# Sheet1.net
KiCad netlist of a schematic drawn in Altium Designer
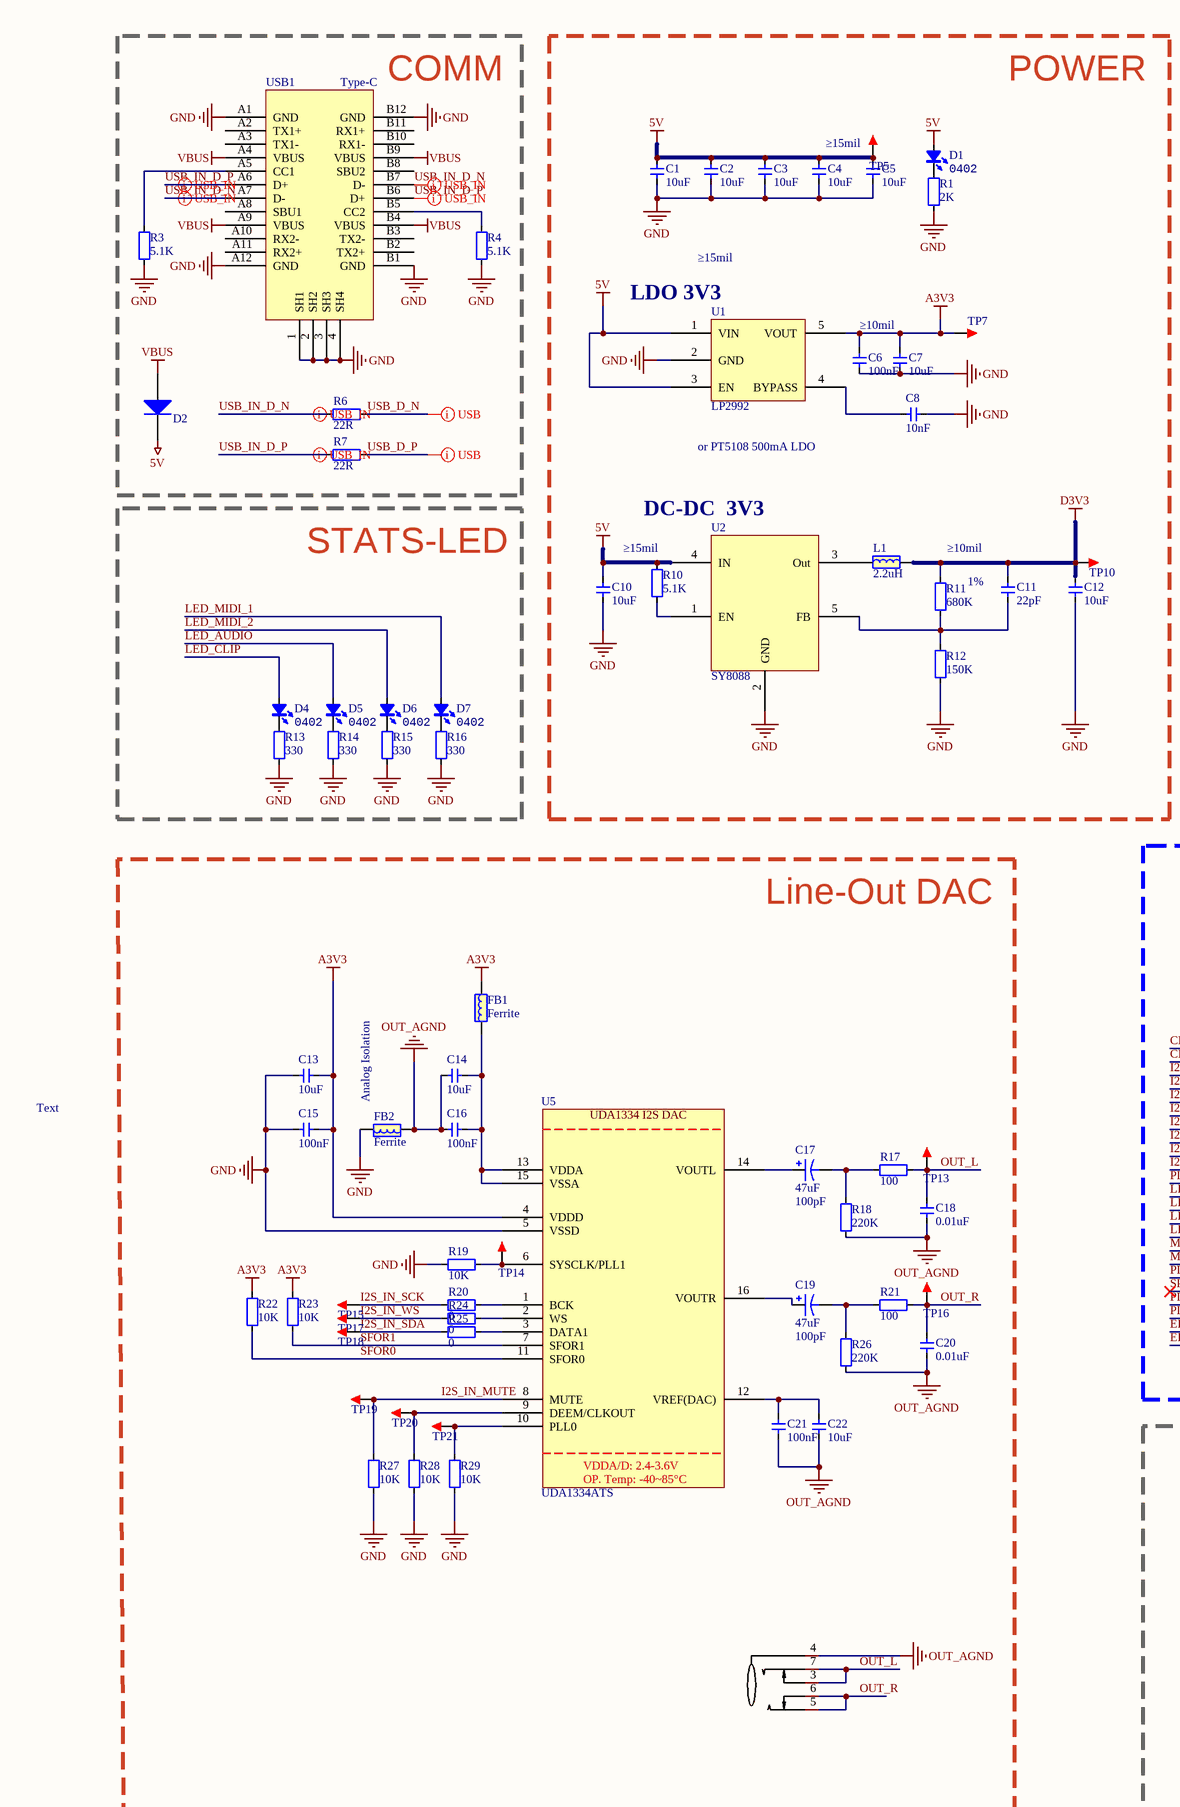
[diagram p0: Sheet1.SchDoc, left]
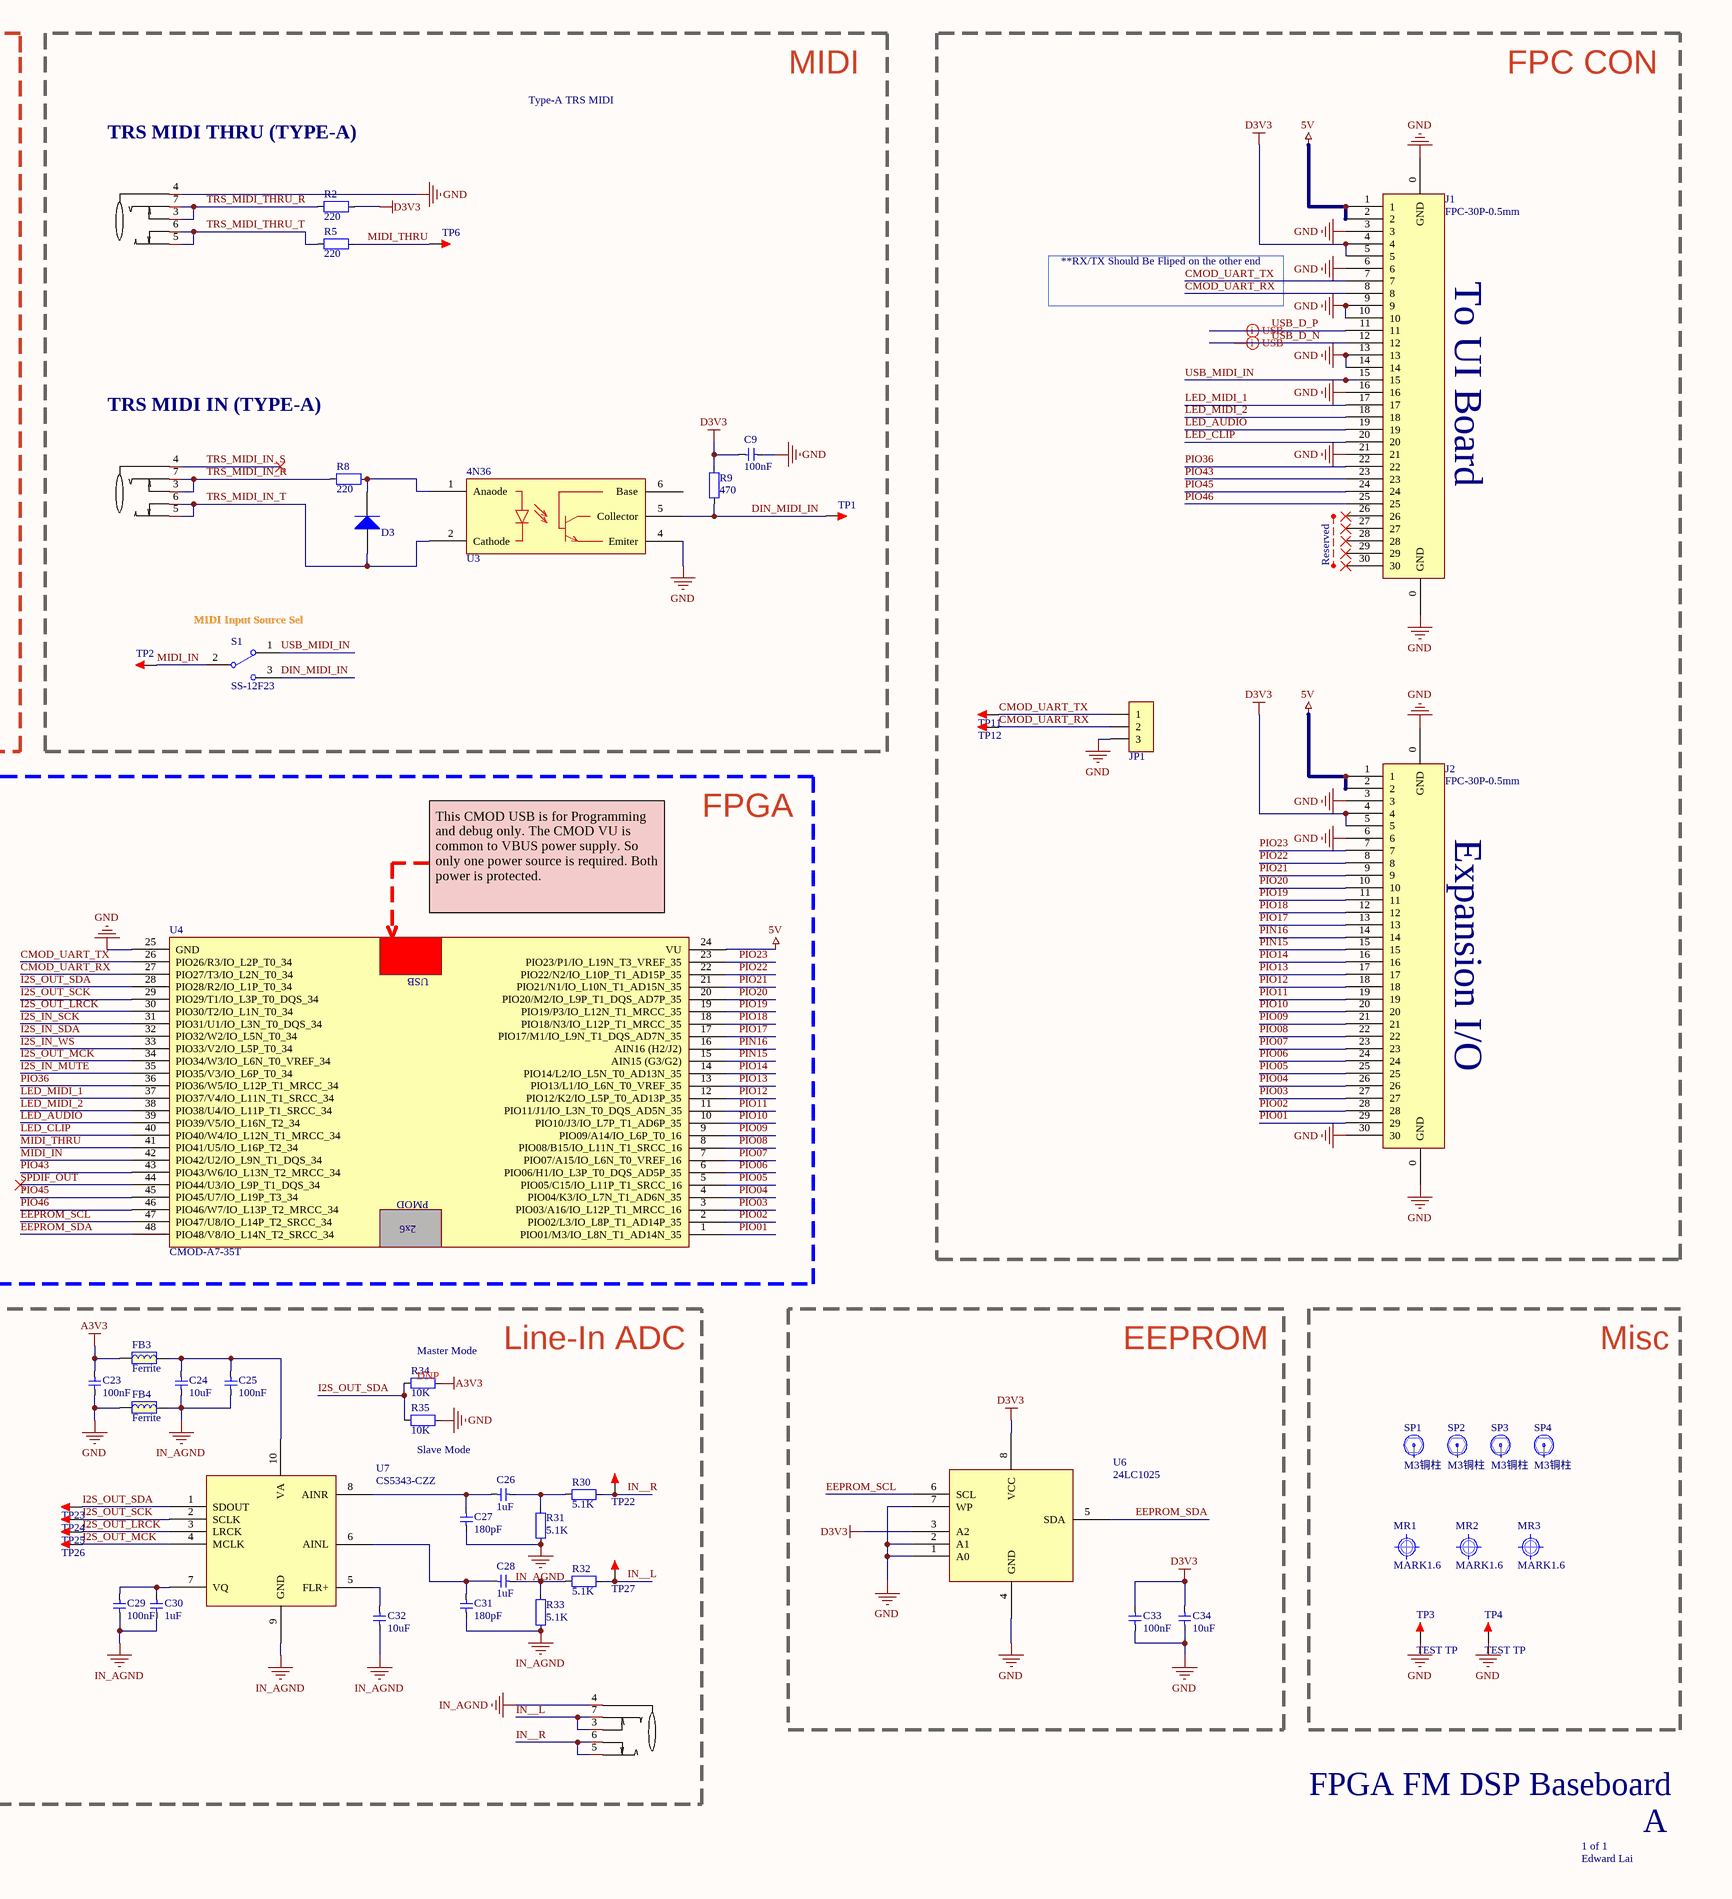
[diagram p1: Sheet1.SchDoc, right]

(export (version "E")
  (design (tool "Eeschema 10.0.6"))
  (components
    (comp (ref "C1")
      (value "10uF")
      (footprint "C0402_L")
      (description "Capacitor")
      (libsource (lib "MyPcbLib") (part "电容-1206"))
    )
    (comp (ref "C2")
      (value "10uF")
      (footprint "C0402_L")
      (description "Capacitor")
      (libsource (lib "MyPcbLib") (part "电容-1206"))
    )
    (comp (ref "C3")
      (value "10uF")
      (footprint "C0402_L")
      (description "Capacitor")
      (libsource (lib "MyPcbLib") (part "电容-1206"))
    )
    (comp (ref "C4")
      (value "10uF")
      (footprint "C0402_L")
      (description "Capacitor")
      (libsource (lib "MyPcbLib") (part "电容-1206"))
    )
    (comp (ref "C5")
      (value "10uF")
      (footprint "C0402_L")
      (description "Capacitor")
      (libsource (lib "MyPcbLib") (part "电容-1206"))
    )
    (comp (ref "C6")
      (value "100nF")
      (footprint "C0402_L")
      (description "Capacitor")
      (libsource (lib "MyPcbLib") (part "电容-0402"))
    )
    (comp (ref "C7")
      (value "10uF")
      (footprint "C0402_L")
      (description "Capacitor")
      (libsource (lib "MyPcbLib") (part "电容-0402"))
    )
    (comp (ref "C8")
      (value "10nF")
      (footprint "C0402_L")
      (description "Capacitor")
      (libsource (lib "MyPcbLib") (part "电容-0402"))
    )
    (comp (ref "C9")
      (value "100nF")
      (footprint "C0402_L")
      (description "Capacitor")
      (libsource (lib "MyPcbLib") (part "电容-0402"))
    )
    (comp (ref "C10")
      (value "10uF")
      (footprint "C0402_L")
      (description "Capacitor")
      (libsource (lib "MyPcbLib") (part "电容-0402"))
    )
    (comp (ref "C11")
      (value "22pF")
      (footprint "C0402_L")
      (description "Capacitor")
      (libsource (lib "MyPcbLib") (part "电容-0402"))
    )
    (comp (ref "C12")
      (value "10uF")
      (footprint "C0402_L")
      (description "Capacitor")
      (libsource (lib "MyPcbLib") (part "电容-0402"))
    )
    (comp (ref "C13")
      (value "10uF")
      (footprint "C0402_L")
      (description "Capacitor")
      (libsource (lib "MyPcbLib") (part "电容-0402"))
    )
    (comp (ref "C14")
      (value "10uF")
      (footprint "C0402_L")
      (description "Capacitor")
      (libsource (lib "MyPcbLib") (part "电容-0402"))
    )
    (comp (ref "C15")
      (value "100nF")
      (footprint "C0402_L")
      (description "Capacitor")
      (libsource (lib "MyPcbLib") (part "电容-0402"))
    )
    (comp (ref "C16")
      (value "100nF")
      (footprint "C0402_L")
      (description "Capacitor")
      (libsource (lib "MyPcbLib") (part "电容-0402"))
    )
    (comp (ref "C17")
      (value "47uF")
      (footprint "CT 5*6 - B")
      (description "Polarized Capacitor SMT")
      (fields (field (name "ALTIUM_VALUE") "100pF") (field (name "PUBLISHER") "Altium Limited"))
      (libsource (lib "Miscellaneous Devices") (part "Cap Pol1"))
    )
    (comp (ref "C18")
      (value "0.01uF")
      (footprint "C0603_L")
      (description "Capacitor")
      (libsource (lib "MyPcbLib") (part "电容-0402"))
    )
    (comp (ref "C19")
      (value "47uF")
      (footprint "CT 5*6 - B")
      (description "Polarized Capacitor SMT")
      (fields (field (name "ALTIUM_VALUE") "100pF") (field (name "PUBLISHER") "Altium Limited"))
      (libsource (lib "Miscellaneous Devices") (part "Cap Pol1"))
    )
    (comp (ref "C20")
      (value "0.01uF")
      (footprint "C0603_L")
      (description "Capacitor")
      (libsource (lib "MyPcbLib") (part "电容-0402"))
    )
    (comp (ref "C21")
      (value "100nF")
      (footprint "C0402_L")
      (description "Capacitor")
      (libsource (lib "MyPcbLib") (part "电容-0402"))
    )
    (comp (ref "C22")
      (value "10uF")
      (footprint "C0402_L")
      (description "Capacitor")
      (libsource (lib "MyPcbLib") (part "电容-0402"))
    )
    (comp (ref "C23")
      (value "100nF")
      (footprint "C0402_L")
      (description "Capacitor")
      (libsource (lib "MyPcbLib") (part "电容-0402"))
    )
    (comp (ref "C24")
      (value "10uF")
      (footprint "C0402_L")
      (description "Capacitor")
      (libsource (lib "MyPcbLib") (part "电容-0402"))
    )
    (comp (ref "C25")
      (value "100nF")
      (footprint "C0402_L")
      (description "Capacitor")
      (libsource (lib "MyPcbLib") (part "电容-0402"))
    )
    (comp (ref "C26")
      (value "1uF")
      (footprint "C0402_L")
      (description "Capacitor")
      (libsource (lib "MyPcbLib") (part "电容-0402"))
    )
    (comp (ref "C27")
      (value "180pF")
      (footprint "C0402_L")
      (description "Capacitor")
      (libsource (lib "MyPcbLib") (part "电容-0402"))
    )
    (comp (ref "C28")
      (value "1uF")
      (footprint "C0402_L")
      (description "Capacitor")
      (libsource (lib "MyPcbLib") (part "电容-0402"))
    )
    (comp (ref "C29")
      (value "100nF")
      (footprint "C0402_L")
      (description "Capacitor")
      (libsource (lib "MyPcbLib") (part "电容-0402"))
    )
    (comp (ref "C30")
      (value "1uF")
      (footprint "C0402_L")
      (description "Capacitor")
      (libsource (lib "MyPcbLib") (part "电容-0402"))
    )
    (comp (ref "C31")
      (value "180pF")
      (footprint "C0402_L")
      (description "Capacitor")
      (libsource (lib "MyPcbLib") (part "电容-0402"))
    )
    (comp (ref "C32")
      (value "10uF")
      (footprint "C0402_L")
      (description "Capacitor")
      (libsource (lib "MyPcbLib") (part "电容-0402"))
    )
    (comp (ref "C33")
      (value "100nF")
      (footprint "C0402_L")
      (description "Capacitor")
      (libsource (lib "MyPcbLib") (part "电容-0402"))
    )
    (comp (ref "C34")
      (value "10uF")
      (footprint "C0402_L")
      (description "Capacitor")
      (libsource (lib "MyPcbLib") (part "电容-0402"))
    )
    (comp (ref "CN1")
      (value "PJ-328-5A")
      (footprint "AUDIO-SMD_PJ-328-5A")
      (fields (field (name "MANUFACTURER") "韩国韩荣"))
      (libsource (lib "altium-import") (part "root_0_PJ-328-5A_"))
    )
    (comp (ref "CN2")
      (value "PJ-328-5A")
      (footprint "AUDIO-SMD_PJ-328-5A")
      (fields (field (name "MANUFACTURER") "韩国韩荣"))
      (libsource (lib "altium-import") (part "root_0_PJ-328-5A_"))
    )
    (comp (ref "CN3")
      (value "PJ-328-5A")
      (footprint "AUDIO-SMD_PJ-328-5A")
      (fields (field (name "MANUFACTURER") "韩国韩荣"))
      (libsource (lib "altium-import") (part "root_0_PJ-328-5A_"))
    )
    (comp (ref "CN4")
      (value "PJ-328-5A")
      (footprint "AUDIO-SMD_PJ-328-5A")
      (fields (field (name "MANUFACTURER") "韩国韩荣"))
      (libsource (lib "altium-import") (part "root_0_mirrored_PJ-328-5A_"))
    )
    (comp (ref "D1")
      (value "color?")
      (footprint "LED0603_R")
      (description "LED")
      (fields (field (name "TYPE") "0402"))
      (libsource (lib "KitSprout") (part "LED_0402"))
    )
    (comp (ref "D2")
      (value "二极管-5B5819WS")
      (footprint "SOD-323")
      (description "40V")
      (libsource (lib "MyPcbLib") (part "二极管-5B5817WS"))
    )
    (comp (ref "D3")
      (value "Diode")
      (footprint "SOD-523")
      (description "1N1418")
      (libsource (lib "0.2 - 二极管-TVS-ESD-整流桥") (part "Diode"))
    )
    (comp (ref "D4")
      (value "color?")
      (footprint "LED0603_R")
      (description "LED")
      (fields (field (name "TYPE") "0402"))
      (libsource (lib "KitSprout") (part "LED_0402"))
    )
    (comp (ref "D5")
      (value "color?")
      (footprint "LED0603_G")
      (description "LED")
      (fields (field (name "TYPE") "0402"))
      (libsource (lib "KitSprout") (part "LED_0402"))
    )
    (comp (ref "D6")
      (value "color?")
      (footprint "LED0603_W")
      (description "LED")
      (fields (field (name "TYPE") "0402"))
      (libsource (lib "KitSprout") (part "LED_0402"))
    )
    (comp (ref "D7")
      (value "color?")
      (footprint "LED0603_W")
      (description "LED")
      (fields (field (name "TYPE") "0402"))
      (libsource (lib "KitSprout") (part "LED_0402"))
    )
    (comp (ref "FB1") (value "Ferrite") (footprint "L0402") (libsource (lib "") (part "电感-201612_2")))
    (comp (ref "FB2") (value "Ferrite") (footprint "L0402") (libsource (lib "MyPcbLib") (part "电感-201612")))
    (comp (ref "FB3") (value "Ferrite") (footprint "L0402") (libsource (lib "") (part "电感-201612_1")))
    (comp (ref "FB4") (value "Ferrite") (footprint "L0402") (libsource (lib "") (part "电感-201612_1")))
    (comp (ref "J1")
      (value "FPC-30P-0.5mm")
      (footprint "FPC0.5-WT-30P")
      (libsource (lib "Schlib2") (part "FPC-30P-0.5mm"))
    )
    (comp (ref "J2")
      (value "FPC-30P-0.5mm")
      (footprint "FPC0.5-WT-30P")
      (libsource (lib "Schlib2") (part "FPC-30P-0.5mm"))
    )
    (comp (ref "JP1")
      (value "HDR-1X3")
      (footprint "XH2.54-LS-3P")
      (description "3P接插件")
      (libsource (lib "5.5 - 2.54mm(100mil)连接器(XH2.54)") (part "Header 3"))
    )
    (comp (ref "L1") (value "2.2uH") (footprint "IND-201612") (libsource (lib "") (part "电感-201612_1")))
    (comp (ref "MR1")
      (value "MARK1.6")
      (footprint "Mark 1.6")
      (description "光学定位点")
      (libsource (lib "0.5 - 按键-开关-蜂鸣器-保险丝-电池-测试点-Mark点") (part "MARK"))
    )
    (comp (ref "MR2")
      (value "MARK1.6")
      (footprint "Mark 1.6")
      (description "光学定位点")
      (libsource (lib "0.5 - 按键-开关-蜂鸣器-保险丝-电池-测试点-Mark点") (part "MARK"))
    )
    (comp (ref "MR3")
      (value "MARK1.6")
      (footprint "Mark 1.6")
      (description "光学定位点")
      (libsource (lib "0.5 - 按键-开关-蜂鸣器-保险丝-电池-测试点-Mark点") (part "MARK"))
    )
    (comp (ref "R1")
      (value "2K")
      (footprint "R0402_L")
      (description "Resistor")
      (libsource (lib "MyPcbLib") (part "电阻-0402"))
    )
    (comp (ref "R2")
      (value "220")
      (footprint "R0402_L")
      (description "Resistor")
      (libsource (lib "") (part "电阻-0402_2"))
    )
    (comp (ref "R3")
      (value "5.1K")
      (footprint "R0402_L")
      (description "Resistor")
      (libsource (lib "") (part "电阻-0402_1"))
    )
    (comp (ref "R4")
      (value "5.1K")
      (footprint "R0402_L")
      (description "Resistor")
      (libsource (lib "") (part "电阻-0402_1"))
    )
    (comp (ref "R5")
      (value "220")
      (footprint "R0402_L")
      (description "Resistor")
      (libsource (lib "") (part "电阻-0402_2"))
    )
    (comp (ref "R6")
      (value "22R")
      (footprint "R0402_L")
      (description "Resistor")
      (libsource (lib "") (part "电阻-0402_3"))
    )
    (comp (ref "R7")
      (value "22R")
      (footprint "R0402_L")
      (description "Resistor")
      (libsource (lib "") (part "电阻-0402_3"))
    )
    (comp (ref "R8")
      (value "220")
      (footprint "R0402_L")
      (description "Resistor")
      (libsource (lib "") (part "电阻-0402_2"))
    )
    (comp (ref "R9")
      (value "470")
      (footprint "R0402_L")
      (description "Resistor")
      (libsource (lib "MyPcbLib") (part "电阻-0402"))
    )
    (comp (ref "R10")
      (value "5.1K")
      (footprint "R0402_L")
      (description "Resistor")
      (libsource (lib "") (part "电阻-0402_1"))
    )
    (comp (ref "R11")
      (value "680K")
      (footprint "R0402_L")
      (description "Resistor")
      (fields (field (name "PARAMETER 1") "1%"))
      (libsource (lib "") (part "电阻-0402_1"))
    )
    (comp (ref "R12")
      (value "150K")
      (footprint "R0402_L")
      (description "Resistor")
      (libsource (lib "") (part "电阻-0402_1"))
    )
    (comp (ref "R13")
      (value "330")
      (footprint "R0402_L")
      (description "Resistor")
      (libsource (lib "MyPcbLib") (part "电阻-0402"))
    )
    (comp (ref "R14")
      (value "330")
      (footprint "R0402_L")
      (description "Resistor")
      (libsource (lib "MyPcbLib") (part "电阻-0402"))
    )
    (comp (ref "R15")
      (value "330")
      (footprint "R0402_L")
      (description "Resistor")
      (libsource (lib "MyPcbLib") (part "电阻-0402"))
    )
    (comp (ref "R16")
      (value "330")
      (footprint "R0402_L")
      (description "Resistor")
      (libsource (lib "MyPcbLib") (part "电阻-0402"))
    )
    (comp (ref "R17")
      (value "100")
      (footprint "R0603_L")
      (description "Resistor")
      (libsource (lib "") (part "电阻-0402_3"))
    )
    (comp (ref "R18")
      (value "220K")
      (footprint "R0603_L")
      (description "Resistor")
      (libsource (lib "") (part "电阻-0402_1"))
    )
    (comp (ref "R19")
      (value "10K")
      (footprint "R0402_L")
      (description "Resistor")
      (libsource (lib "") (part "电阻-0402_3"))
    )
    (comp (ref "R20")
      (value "0")
      (footprint "R0402_L")
      (description "Resistor")
      (libsource (lib "") (part "电阻-0402_2"))
    )
    (comp (ref "R21")
      (value "100")
      (footprint "R0603_L")
      (description "Resistor")
      (libsource (lib "") (part "电阻-0402_3"))
    )
    (comp (ref "R22")
      (value "10K")
      (footprint "R0402_L")
      (description "Resistor")
      (libsource (lib "") (part "电阻-0402_1"))
    )
    (comp (ref "R23")
      (value "10K")
      (footprint "R0402_L")
      (description "Resistor")
      (libsource (lib "") (part "电阻-0402_1"))
    )
    (comp (ref "R24")
      (value "0")
      (footprint "R0402_L")
      (description "Resistor")
      (libsource (lib "") (part "电阻-0402_2"))
    )
    (comp (ref "R25")
      (value "0")
      (footprint "R0402_L")
      (description "Resistor")
      (libsource (lib "") (part "电阻-0402_2"))
    )
    (comp (ref "R26")
      (value "220K")
      (footprint "R0603_L")
      (description "Resistor")
      (libsource (lib "") (part "电阻-0402_1"))
    )
    (comp (ref "R27")
      (value "10K")
      (footprint "R0402_L")
      (description "Resistor")
      (libsource (lib "") (part "电阻-0402_1"))
    )
    (comp (ref "R28")
      (value "10K")
      (footprint "R0402_L")
      (description "Resistor")
      (libsource (lib "") (part "电阻-0402_1"))
    )
    (comp (ref "R29")
      (value "10K")
      (footprint "R0402_L")
      (description "Resistor")
      (libsource (lib "") (part "电阻-0402_1"))
    )
    (comp (ref "R30")
      (value "5.1K")
      (footprint "R0402_L")
      (description "Resistor")
      (libsource (lib "") (part "电阻-0402_3"))
    )
    (comp (ref "R31")
      (value "5.1K")
      (footprint "R0402_L")
      (description "Resistor")
      (libsource (lib "") (part "电阻-0402_1"))
    )
    (comp (ref "R32")
      (value "5.1K")
      (footprint "R0402_L")
      (description "Resistor")
      (libsource (lib "") (part "电阻-0402_2"))
    )
    (comp (ref "R33")
      (value "5.1K")
      (footprint "R0402_L")
      (description "Resistor")
      (libsource (lib "") (part "电阻-0402_1"))
    )
    (comp (ref "R34")
      (value "10K")
      (footprint "R0402_L")
      (description "Resistor")
      (libsource (lib "") (part "电阻-0402_3"))
    )
    (comp (ref "R35")
      (value "10K")
      (footprint "R0402_L")
      (description "Resistor")
      (libsource (lib "") (part "电阻-0402_3"))
    )
    (comp (ref "S1")
      (value "SS-12F23")
      (footprint "MSK-12C01-07")
      (description "1路波动开关")
      (libsource (lib "0.5 - 按键-开关-蜂鸣器-保险丝-电池-测试点-Mark点") (part "SSW-1P"))
    )
    (comp (ref "SP1")
      (value "M3铜柱")
      (footprint "M3x8_N")
      (description "铜柱")
      (libsource (lib "0.5 - 按键-开关-蜂鸣器-保险丝-电池-测试点-Mark点") (part "铜柱大焊盘"))
    )
    (comp (ref "SP2")
      (value "M3铜柱")
      (footprint "M3x8_N")
      (description "铜柱")
      (libsource (lib "0.5 - 按键-开关-蜂鸣器-保险丝-电池-测试点-Mark点") (part "铜柱大焊盘"))
    )
    (comp (ref "SP3")
      (value "M3铜柱")
      (footprint "M3x8_N")
      (description "铜柱")
      (libsource (lib "0.5 - 按键-开关-蜂鸣器-保险丝-电池-测试点-Mark点") (part "铜柱大焊盘"))
    )
    (comp (ref "SP4")
      (value "M3铜柱")
      (footprint "M3x8_N")
      (description "铜柱")
      (libsource (lib "0.5 - 按键-开关-蜂鸣器-保险丝-电池-测试点-Mark点") (part "铜柱大焊盘"))
    )
    (comp (ref "TP1")
      (value "DIN_MIDI_IN")
      (footprint "TEST 1.2")
      (description "测试环")
      (libsource (lib "0.5 - 按键-开关-蜂鸣器-保险丝-电池-测试点-Mark点") (part "TEST TP"))
    )
    (comp (ref "TP2")
      (value "MIDI_IN")
      (footprint "TEST 1.2")
      (description "测试环")
      (libsource (lib "0.5 - 按键-开关-蜂鸣器-保险丝-电池-测试点-Mark点") (part "TEST TP"))
    )
    (comp (ref "TP3")
      (value "TEST TP")
      (footprint "TEST 1.2")
      (description "测试环")
      (libsource (lib "0.5 - 按键-开关-蜂鸣器-保险丝-电池-测试点-Mark点") (part "TEST TP"))
    )
    (comp (ref "TP4")
      (value "TEST TP")
      (footprint "TEST 1.2")
      (description "测试环")
      (libsource (lib "0.5 - 按键-开关-蜂鸣器-保险丝-电池-测试点-Mark点") (part "TEST TP"))
    )
    (comp (ref "TP5")
      (value "DIN_MIDI_IN")
      (footprint "TEST 1.2")
      (description "测试环")
      (libsource (lib "0.5 - 按键-开关-蜂鸣器-保险丝-电池-测试点-Mark点") (part "TEST TP"))
    )
    (comp (ref "TP6")
      (value "DIN_MIDI_IN")
      (footprint "TEST 1.2")
      (description "测试环")
      (libsource (lib "0.5 - 按键-开关-蜂鸣器-保险丝-电池-测试点-Mark点") (part "TEST TP"))
    )
    (comp (ref "TP7")
      (value "DIN_MIDI_IN")
      (footprint "TEST 1.2")
      (description "测试环")
      (libsource (lib "0.5 - 按键-开关-蜂鸣器-保险丝-电池-测试点-Mark点") (part "TEST TP"))
    )
    (comp (ref "TP10")
      (value "DIN_MIDI_IN")
      (footprint "TEST 1.2")
      (description "测试环")
      (libsource (lib "0.5 - 按键-开关-蜂鸣器-保险丝-电池-测试点-Mark点") (part "TEST TP"))
    )
    (comp (ref "TP11")
      (value "DIN_MIDI_IN")
      (footprint "TEST 1.2")
      (description "测试环")
      (libsource (lib "0.5 - 按键-开关-蜂鸣器-保险丝-电池-测试点-Mark点") (part "TEST TP"))
    )
    (comp (ref "TP12")
      (value "DIN_MIDI_IN")
      (footprint "TEST 1.2")
      (description "测试环")
      (libsource (lib "0.5 - 按键-开关-蜂鸣器-保险丝-电池-测试点-Mark点") (part "TEST TP"))
    )
    (comp (ref "TP13")
      (value "DIN_MIDI_IN")
      (footprint "TEST 1.2")
      (description "测试环")
      (libsource (lib "0.5 - 按键-开关-蜂鸣器-保险丝-电池-测试点-Mark点") (part "TEST TP"))
    )
    (comp (ref "TP14")
      (value "DIN_MIDI_IN")
      (footprint "TEST 1.2")
      (description "测试环")
      (libsource (lib "0.5 - 按键-开关-蜂鸣器-保险丝-电池-测试点-Mark点") (part "TEST TP"))
    )
    (comp (ref "TP15")
      (value "DIN_MIDI_IN")
      (footprint "TEST 1.2")
      (description "测试环")
      (libsource (lib "0.5 - 按键-开关-蜂鸣器-保险丝-电池-测试点-Mark点") (part "TEST TP"))
    )
    (comp (ref "TP16")
      (value "DIN_MIDI_IN")
      (footprint "TEST 1.2")
      (description "测试环")
      (libsource (lib "0.5 - 按键-开关-蜂鸣器-保险丝-电池-测试点-Mark点") (part "TEST TP"))
    )
    (comp (ref "TP17")
      (value "DIN_MIDI_IN")
      (footprint "TEST 1.2")
      (description "测试环")
      (libsource (lib "0.5 - 按键-开关-蜂鸣器-保险丝-电池-测试点-Mark点") (part "TEST TP"))
    )
    (comp (ref "TP18")
      (value "DIN_MIDI_IN")
      (footprint "TEST 1.2")
      (description "测试环")
      (libsource (lib "0.5 - 按键-开关-蜂鸣器-保险丝-电池-测试点-Mark点") (part "TEST TP"))
    )
    (comp (ref "TP19")
      (value "DIN_MIDI_IN")
      (footprint "TEST 1.2")
      (description "测试环")
      (libsource (lib "0.5 - 按键-开关-蜂鸣器-保险丝-电池-测试点-Mark点") (part "TEST TP"))
    )
    (comp (ref "TP20")
      (value "DIN_MIDI_IN")
      (footprint "TEST 1.2")
      (description "测试环")
      (libsource (lib "0.5 - 按键-开关-蜂鸣器-保险丝-电池-测试点-Mark点") (part "TEST TP"))
    )
    (comp (ref "TP21")
      (value "DIN_MIDI_IN")
      (footprint "TEST 1.2")
      (description "测试环")
      (libsource (lib "0.5 - 按键-开关-蜂鸣器-保险丝-电池-测试点-Mark点") (part "TEST TP"))
    )
    (comp (ref "TP22")
      (value "DIN_MIDI_IN")
      (footprint "TEST 1.2")
      (description "测试环")
      (libsource (lib "0.5 - 按键-开关-蜂鸣器-保险丝-电池-测试点-Mark点") (part "TEST TP"))
    )
    (comp (ref "TP23")
      (value "DIN_MIDI_IN")
      (footprint "TEST 1.2")
      (description "测试环")
      (libsource (lib "0.5 - 按键-开关-蜂鸣器-保险丝-电池-测试点-Mark点") (part "TEST TP"))
    )
    (comp (ref "TP24")
      (value "DIN_MIDI_IN")
      (footprint "TEST 1.2")
      (description "测试环")
      (libsource (lib "0.5 - 按键-开关-蜂鸣器-保险丝-电池-测试点-Mark点") (part "TEST TP"))
    )
    (comp (ref "TP25")
      (value "DIN_MIDI_IN")
      (footprint "TEST 1.2")
      (description "测试环")
      (libsource (lib "0.5 - 按键-开关-蜂鸣器-保险丝-电池-测试点-Mark点") (part "TEST TP"))
    )
    (comp (ref "TP26")
      (value "DIN_MIDI_IN")
      (footprint "TEST 1.2")
      (description "测试环")
      (libsource (lib "0.5 - 按键-开关-蜂鸣器-保险丝-电池-测试点-Mark点") (part "TEST TP"))
    )
    (comp (ref "TP27")
      (value "DIN_MIDI_IN")
      (footprint "TEST 1.2")
      (description "测试环")
      (libsource (lib "0.5 - 按键-开关-蜂鸣器-保险丝-电池-测试点-Mark点") (part "TEST TP"))
    )
    (comp (ref "U1") (value "LP2992") (footprint "SOT23-5M") (libsource (lib "Schlib2") (part "LP2992")))
    (comp (ref "U2")
      (value "SY8088")
      (footprint "SOT23-5")
      (description "SY8088 High Efficiency 1.5MHz, 1A  \r\nSynchronous Step Down Regulator")
      (libsource (lib "Schlib2") (part "SY8088"))
    )
    (comp (ref "U3")
      (value "4N36")
      (footprint "OPTOCOUPLER_H11F3SR2M")
      (description "4N36\r\n6-Pin General Purpose Phototransistor Optocouplers")
      (libsource (lib "Schlib2") (part "4N36"))
    )
    (comp (ref "U4")
      (value "CMOD-A7-35T")
      (footprint "DIP48")
      (description "Digilent CMOD A7 35T")
      (libsource (lib "Schlib2") (part "CMOD-A7-35T"))
    )
    (comp (ref "U5")
      (value "UDA1334ATS")
      (footprint "SSOP16")
      (libsource (lib "Schlib2") (part "UDA1334ATS"))
    )
    (comp (ref "U6")
      (value "24LC1025")
      (footprint "SOIC-8")
      (description "24LC1025 EEPROM")
      (libsource (lib "Schlib2") (part "24LC1025"))
    )
    (comp (ref "U7")
      (value "CS5343-CZZ")
      (footprint "MSOP10_M")
      (description "98dB 96kHz Multi-Bit Audio ADC")
      (libsource (lib "Schlib2") (part "CS5343-CZZ"))
    )
    (comp (ref "USB1")
      (value "Type-C")
      (footprint "Type-C-TOP")
      (libsource (lib "MyPcbLib") (part "USB-Type-C-TOP"))
    )
  )
  (nets
    (net (code "1") (name "/CMOD_UART_RX") (class "Default")
      (node (ref "J1") (pin "8") (pinfunction "8_8") (pintype "passive"))
      (node (ref "JP1") (pin "2") (pinfunction "2_2") (pintype "passive"))
      (node (ref "TP12") (pin "1") (pinfunction "1_1") (pintype "passive"))
      (node (ref "U4") (pin "27") (pinfunction "PIO27/T3/IO_L2N_T0_34_27") (pintype "passive"))
    )
    (net (code "2") (name "/CMOD_UART_TX") (class "Default")
      (node (ref "J1") (pin "7") (pinfunction "7_7") (pintype "passive"))
      (node (ref "JP1") (pin "1") (pinfunction "1_1") (pintype "passive"))
      (node (ref "TP11") (pin "1") (pinfunction "1_1") (pintype "passive"))
      (node (ref "U4") (pin "26") (pinfunction "PIO26/R3/IO_L2P_T0_34_26") (pintype "passive"))
    )
    (net (code "3") (name "/DIN_MIDI_IN") (class "Default")
      (node (ref "R9") (pin "1") (pinfunction "1_1") (pintype "passive"))
      (node (ref "S1") (pin "3") (pinfunction "3_3") (pintype "passive"))
      (node (ref "TP1") (pin "1") (pinfunction "1_1") (pintype "passive"))
      (node (ref "U3") (pin "5") (pinfunction "Collector_5") (pintype "passive"))
    )
    (net (code "4") (name "/EEPROM_SCL") (class "Default")
      (node (ref "U4") (pin "47") (pinfunction "PIO47/U8/IO_L14P_T2_SRCC_34_47") (pintype "passive"))
      (node (ref "U6") (pin "6") (pinfunction "SCL_6") (pintype "passive"))
    )
    (net (code "5") (name "/EEPROM_SDA") (class "Default")
      (node (ref "U4") (pin "48") (pinfunction "PIO48/V8/IO_L14N_T2_SRCC_34_48") (pintype "passive"))
      (node (ref "U6") (pin "5") (pinfunction "SDA_5") (pintype "passive"))
    )
    (net (code "6") (name "/I2S_IN_MUTE") (class "Default")
      (node (ref "R27") (pin "1") (pinfunction "1_1") (pintype "passive"))
      (node (ref "TP19") (pin "1") (pinfunction "1_1") (pintype "passive"))
      (node (ref "U4") (pin "35") (pinfunction "PIO35/V3/IO_L6P_T0_34_35") (pintype "passive"))
      (node (ref "U5") (pin "8") (pinfunction "MUTE_8") (pintype "passive"))
    )
    (net (code "7") (name "/I2S_IN_SCK") (class "Default")
      (node (ref "R20") (pin "1") (pinfunction "1_1") (pintype "passive"))
      (node (ref "TP15") (pin "1") (pinfunction "1_1") (pintype "passive"))
      (node (ref "U4") (pin "31") (pinfunction "PIO31/U1/IO_L3N_T0_DQS_34_31") (pintype "passive"))
    )
    (net (code "8") (name "/I2S_IN_SDA") (class "Default")
      (node (ref "R25") (pin "1") (pinfunction "1_1") (pintype "passive"))
      (node (ref "TP18") (pin "1") (pinfunction "1_1") (pintype "passive"))
      (node (ref "U4") (pin "32") (pinfunction "PIO32/W2/IO_L5N_T0_34_32") (pintype "passive"))
    )
    (net (code "9") (name "/I2S_IN_WS") (class "Default")
      (node (ref "R24") (pin "1") (pinfunction "1_1") (pintype "passive"))
      (node (ref "TP17") (pin "1") (pinfunction "1_1") (pintype "passive"))
      (node (ref "U4") (pin "33") (pinfunction "PIO33/V2/IO_L5P_T0_34_33") (pintype "passive"))
    )
    (net (code "10") (name "/I2S_OUT_LRCK") (class "Default")
      (node (ref "TP25") (pin "1") (pinfunction "1_1") (pintype "passive"))
      (node (ref "U4") (pin "30") (pinfunction "PIO30/T2/IO_L1N_T0_34_30") (pintype "passive"))
      (node (ref "U7") (pin "3") (pinfunction "LRCK_3") (pintype "passive"))
    )
    (net (code "11") (name "/I2S_OUT_MCK") (class "Default")
      (node (ref "TP26") (pin "1") (pinfunction "1_1") (pintype "passive"))
      (node (ref "U4") (pin "34") (pinfunction "PIO34/W3/IO_L6N_T0_VREF_34_34") (pintype "passive"))
      (node (ref "U7") (pin "4") (pinfunction "MCLK_4") (pintype "passive"))
    )
    (net (code "12") (name "/I2S_OUT_SCK") (class "Default")
      (node (ref "TP24") (pin "1") (pinfunction "1_1") (pintype "passive"))
      (node (ref "U4") (pin "29") (pinfunction "PIO29/T1/IO_L3P_T0_DQS_34_29") (pintype "passive"))
      (node (ref "U7") (pin "2") (pinfunction "SCLK_2") (pintype "passive"))
    )
    (net (code "13") (name "/I2S_OUT_SDA") (class "Default")
      (node (ref "R34") (pin "2") (pinfunction "2_2") (pintype "passive"))
      (node (ref "R35") (pin "2") (pinfunction "2_2") (pintype "passive"))
      (node (ref "TP23") (pin "1") (pinfunction "1_1") (pintype "passive"))
      (node (ref "U4") (pin "28") (pinfunction "PIO28/R2/IO_L1P_T0_34_28") (pintype "passive"))
      (node (ref "U7") (pin "1") (pinfunction "SDOUT_1") (pintype "passive"))
    )
    (net (code "14") (name "/IN__L") (class "Default")
      (node (ref "CN4") (pin "3") (pinfunction "3_3") (pintype "passive"))
      (node (ref "CN4") (pin "7") (pinfunction "7_7") (pintype "passive"))
      (node (ref "R32") (pin "2") (pinfunction "2_2") (pintype "passive"))
      (node (ref "TP27") (pin "1") (pinfunction "1_1") (pintype "passive"))
    )
    (net (code "15") (name "/IN__R") (class "Default")
      (node (ref "CN4") (pin "5") (pinfunction "5_5") (pintype "passive"))
      (node (ref "CN4") (pin "6") (pinfunction "6_6") (pintype "passive"))
      (node (ref "R30") (pin "1") (pinfunction "1_1") (pintype "passive"))
      (node (ref "TP22") (pin "1") (pinfunction "1_1") (pintype "passive"))
    )
    (net (code "16") (name "/LED_AUDIO") (class "Default")
      (node (ref "D5") (pin "1") (pinfunction "A_1") (pintype "passive"))
      (node (ref "J1") (pin "19") (pinfunction "19_19") (pintype "passive"))
      (node (ref "U4") (pin "39") (pinfunction "PIO39/V5/IO_L16N_T2_34_39") (pintype "passive"))
    )
    (net (code "17") (name "/LED_CLIP") (class "Default")
      (node (ref "D4") (pin "1") (pinfunction "A_1") (pintype "passive"))
      (node (ref "J1") (pin "20") (pinfunction "20_20") (pintype "passive"))
      (node (ref "U4") (pin "40") (pinfunction "PIO40/W4/IO_L12N_T1_MRCC_34_40") (pintype "passive"))
    )
    (net (code "18") (name "/LED_MIDI_1") (class "Default")
      (node (ref "D7") (pin "1") (pinfunction "A_1") (pintype "passive"))
      (node (ref "J1") (pin "17") (pinfunction "17_17") (pintype "passive"))
      (node (ref "U4") (pin "37") (pinfunction "PIO37/V4/IO_L11N_T1_SRCC_34_37") (pintype "passive"))
    )
    (net (code "19") (name "/LED_MIDI_2") (class "Default")
      (node (ref "D6") (pin "1") (pinfunction "A_1") (pintype "passive"))
      (node (ref "J1") (pin "18") (pinfunction "18_18") (pintype "passive"))
      (node (ref "U4") (pin "38") (pinfunction "PIO38/U4/IO_L11P_T1_SRCC_34_38") (pintype "passive"))
    )
    (net (code "20") (name "/MIDI_IN") (class "Default")
      (node (ref "S1") (pin "2") (pinfunction "2_2") (pintype "passive"))
      (node (ref "TP2") (pin "1") (pinfunction "1_1") (pintype "passive"))
      (node (ref "U4") (pin "42") (pinfunction "PIO42/U2/IO_L9N_T1_DQS_34_42") (pintype "passive"))
    )
    (net (code "21") (name "/MIDI_THRU") (class "Default")
      (node (ref "R5") (pin "2") (pinfunction "2_2") (pintype "passive"))
      (node (ref "TP6") (pin "1") (pinfunction "1_1") (pintype "passive"))
      (node (ref "U4") (pin "41") (pinfunction "PIO41/U5/IO_L16P_T2_34_41") (pintype "passive"))
    )
    (net (code "22") (name "/OUT_L") (class "Default")
      (node (ref "C18") (pin "2") (pinfunction "2_2") (pintype "passive"))
      (node (ref "CN3") (pin "3") (pinfunction "3_3") (pintype "passive"))
      (node (ref "CN3") (pin "7") (pinfunction "7_7") (pintype "passive"))
      (node (ref "R17") (pin "1") (pinfunction "1_1") (pintype "passive"))
      (node (ref "TP13") (pin "1") (pinfunction "1_1") (pintype "passive"))
    )
    (net (code "23") (name "/OUT_R") (class "Default")
      (node (ref "C20") (pin "2") (pinfunction "2_2") (pintype "passive"))
      (node (ref "CN3") (pin "5") (pinfunction "5_5") (pintype "passive"))
      (node (ref "CN3") (pin "6") (pinfunction "6_6") (pintype "passive"))
      (node (ref "R21") (pin "1") (pinfunction "1_1") (pintype "passive"))
      (node (ref "TP16") (pin "1") (pinfunction "1_1") (pintype "passive"))
    )
    (net (code "24") (name "/PIN15") (class "Default")
      (node (ref "J2") (pin "15") (pinfunction "15_15") (pintype "passive"))
      (node (ref "U4") (pin "15") (pinfunction "AIN15_(G3/G2)_15") (pintype "passive"))
    )
    (net (code "25") (name "/PIN16") (class "Default")
      (node (ref "J2") (pin "14") (pinfunction "14_14") (pintype "passive"))
      (node (ref "U4") (pin "16") (pinfunction "AIN16_(H2/J2)_16") (pintype "passive"))
    )
    (net (code "26") (name "/PIO01") (class "Default")
      (node (ref "J2") (pin "29") (pinfunction "29_29") (pintype "passive"))
      (node (ref "U4") (pin "1") (pinfunction "PIO01/M3/IO_L8N_T1_AD14N_35_1") (pintype "passive"))
    )
    (net (code "27") (name "/PIO02") (class "Default")
      (node (ref "J2") (pin "28") (pinfunction "28_28") (pintype "passive"))
      (node (ref "U4") (pin "2") (pinfunction "PIO02/L3/IO_L8P_T1_AD14P_35_2") (pintype "passive"))
    )
    (net (code "28") (name "/PIO03") (class "Default")
      (node (ref "J2") (pin "27") (pinfunction "27_27") (pintype "passive"))
      (node (ref "U4") (pin "3") (pinfunction "PIO03/A16/IO_L12P_T1_MRCC_16_3") (pintype "passive"))
    )
    (net (code "29") (name "/PIO04") (class "Default")
      (node (ref "J2") (pin "26") (pinfunction "26_26") (pintype "passive"))
      (node (ref "U4") (pin "4") (pinfunction "PIO04/K3/IO_L7N_T1_AD6N_35_4") (pintype "passive"))
    )
    (net (code "30") (name "/PIO05") (class "Default")
      (node (ref "J2") (pin "25") (pinfunction "25_25") (pintype "passive"))
      (node (ref "U4") (pin "5") (pinfunction "PIO05/C15/IO_L11P_T1_SRCC_16_5") (pintype "passive"))
    )
    (net (code "31") (name "/PIO06") (class "Default")
      (node (ref "J2") (pin "24") (pinfunction "24_24") (pintype "passive"))
      (node (ref "U4") (pin "6") (pinfunction "PIO06/H1/IO_L3P_T0_DQS_AD5P_35_6") (pintype "passive"))
    )
    (net (code "32") (name "/PIO07") (class "Default")
      (node (ref "J2") (pin "23") (pinfunction "23_23") (pintype "passive"))
      (node (ref "U4") (pin "7") (pinfunction "PIO07/A15/IO_L6N_T0_VREF_16_7") (pintype "passive"))
    )
    (net (code "33") (name "/PIO08") (class "Default")
      (node (ref "J2") (pin "22") (pinfunction "22_22") (pintype "passive"))
      (node (ref "U4") (pin "8") (pinfunction "PIO08/B15/IO_L11N_T1_SRCC_16_8") (pintype "passive"))
    )
    (net (code "34") (name "/PIO09") (class "Default")
      (node (ref "J2") (pin "21") (pinfunction "21_21") (pintype "passive"))
      (node (ref "U4") (pin "9") (pinfunction "PIO09/A14/IO_L6P_T0_16_9") (pintype "passive"))
    )
    (net (code "35") (name "/PIO10") (class "Default")
      (node (ref "J2") (pin "20") (pinfunction "20_20") (pintype "passive"))
      (node (ref "U4") (pin "10") (pinfunction "PIO10/J3/IO_L7P_T1_AD6P_35_10") (pintype "passive"))
    )
    (net (code "36") (name "/PIO11") (class "Default")
      (node (ref "J2") (pin "19") (pinfunction "19_19") (pintype "passive"))
      (node (ref "U4") (pin "11") (pinfunction "PIO11/J1/IO_L3N_T0_DQS_AD5N_35_11") (pintype "passive"))
    )
    (net (code "37") (name "/PIO12") (class "Default")
      (node (ref "J2") (pin "18") (pinfunction "18_18") (pintype "passive"))
      (node (ref "U4") (pin "12") (pinfunction "PIO12/K2/IO_L5P_T0_AD13P_35_12") (pintype "passive"))
    )
    (net (code "38") (name "/PIO13") (class "Default")
      (node (ref "J2") (pin "17") (pinfunction "17_17") (pintype "passive"))
      (node (ref "U4") (pin "13") (pinfunction "PIO13/L1/IO_L6N_T0_VREF_35_13") (pintype "passive"))
    )
    (net (code "39") (name "/PIO14") (class "Default")
      (node (ref "J2") (pin "16") (pinfunction "16_16") (pintype "passive"))
      (node (ref "U4") (pin "14") (pinfunction "PIO14/L2/IO_L5N_T0_AD13N_35_14") (pintype "passive"))
    )
    (net (code "40") (name "/PIO17") (class "Default")
      (node (ref "J2") (pin "13") (pinfunction "13_13") (pintype "passive"))
      (node (ref "U4") (pin "17") (pinfunction "PIO17/M1/IO_L9N_T1_DQS_AD7N_35_17") (pintype "passive"))
    )
    (net (code "41") (name "/PIO18") (class "Default")
      (node (ref "J2") (pin "12") (pinfunction "12_12") (pintype "passive"))
      (node (ref "U4") (pin "18") (pinfunction "PIO18/N3/IO_L12P_T1_MRCC_35_18") (pintype "passive"))
    )
    (net (code "42") (name "/PIO19") (class "Default")
      (node (ref "J2") (pin "11") (pinfunction "11_11") (pintype "passive"))
      (node (ref "U4") (pin "19") (pinfunction "PIO19/P3/IO_L12N_T1_MRCC_35_19") (pintype "passive"))
    )
    (net (code "43") (name "/PIO20") (class "Default")
      (node (ref "J2") (pin "10") (pinfunction "10_10") (pintype "passive"))
      (node (ref "U4") (pin "20") (pinfunction "PIO20/M2/IO_L9P_T1_DQS_AD7P_35_20") (pintype "passive"))
    )
    (net (code "44") (name "/PIO21") (class "Default")
      (node (ref "J2") (pin "9") (pinfunction "9_9") (pintype "passive"))
      (node (ref "U4") (pin "21") (pinfunction "PIO21/N1/IO_L10N_T1_AD15N_35_21") (pintype "passive"))
    )
    (net (code "45") (name "/PIO22") (class "Default")
      (node (ref "J2") (pin "8") (pinfunction "8_8") (pintype "passive"))
      (node (ref "U4") (pin "22") (pinfunction "PIO22/N2/IO_L10P_T1_AD15P_35_22") (pintype "passive"))
    )
    (net (code "46") (name "/PIO23") (class "Default")
      (node (ref "J2") (pin "7") (pinfunction "7_7") (pintype "passive"))
      (node (ref "U4") (pin "23") (pinfunction "PIO23/P1/IO_L19N_T3_VREF_35_23") (pintype "passive"))
    )
    (net (code "47") (name "/PIO36") (class "Default")
      (node (ref "J1") (pin "22") (pinfunction "22_22") (pintype "passive"))
      (node (ref "U4") (pin "36") (pinfunction "PIO36/W5/IO_L12P_T1_MRCC_34_36") (pintype "passive"))
    )
    (net (code "48") (name "/PIO43") (class "Default")
      (node (ref "J1") (pin "23") (pinfunction "23_23") (pintype "passive"))
      (node (ref "U4") (pin "43") (pinfunction "PIO43/W6/IO_L13N_T2_MRCC_34_43") (pintype "passive"))
    )
    (net (code "49") (name "/PIO45") (class "Default")
      (node (ref "J1") (pin "24") (pinfunction "24_24") (pintype "passive"))
      (node (ref "U4") (pin "45") (pinfunction "PIO45/U7/IO_L19P_T3_34_45") (pintype "passive"))
    )
    (net (code "50") (name "/PIO46") (class "Default")
      (node (ref "J1") (pin "25") (pinfunction "25_25") (pintype "passive"))
      (node (ref "U4") (pin "46") (pinfunction "PIO46/W7/IO_L13P_T2_MRCC_34_46") (pintype "passive"))
    )
    (net (code "51") (name "/SFOR0") (class "Default")
      (node (ref "R22") (pin "2") (pinfunction "2_2") (pintype "passive"))
      (node (ref "U5") (pin "11") (pinfunction "SFOR0_11") (pintype "passive"))
    )
    (net (code "52") (name "/SFOR1") (class "Default")
      (node (ref "R23") (pin "2") (pinfunction "2_2") (pintype "passive"))
      (node (ref "U5") (pin "7") (pinfunction "SFOR1_7") (pintype "passive"))
    )
    (net (code "53") (name "/SPDIF_OUT") (class "Default")
      (node (ref "U4") (pin "44") (pinfunction "PIO44/U3/IO_L9P_T1_DQS_34_44") (pintype "passive+no_connect"))
    )
    (net (code "54") (name "/TRS_MIDI_IN_R") (class "Default")
      (node (ref "CN2") (pin "3") (pinfunction "3_3") (pintype "passive"))
      (node (ref "CN2") (pin "7") (pinfunction "7_7") (pintype "passive"))
      (node (ref "R8") (pin "1") (pinfunction "1_1") (pintype "passive"))
    )
    (net (code "55") (name "/TRS_MIDI_IN_S") (class "Default")
      (node (ref "CN2") (pin "4") (pinfunction "4_4") (pintype "passive+no_connect"))
    )
    (net (code "56") (name "/TRS_MIDI_IN_T") (class "Default")
      (node (ref "CN2") (pin "5") (pinfunction "5_5") (pintype "passive"))
      (node (ref "CN2") (pin "6") (pinfunction "6_6") (pintype "passive"))
      (node (ref "D3") (pin "1") (pinfunction "A_1") (pintype "passive"))
      (node (ref "U3") (pin "2") (pinfunction "Cathode_2") (pintype "passive"))
    )
    (net (code "57") (name "/TRS_MIDI_THRU_R") (class "Default")
      (node (ref "CN1") (pin "3") (pinfunction "3_3") (pintype "passive"))
      (node (ref "CN1") (pin "7") (pinfunction "7_7") (pintype "passive"))
      (node (ref "R2") (pin "1") (pinfunction "1_1") (pintype "passive"))
    )
    (net (code "58") (name "/TRS_MIDI_THRU_T") (class "Default")
      (node (ref "CN1") (pin "5") (pinfunction "5_5") (pintype "passive"))
      (node (ref "CN1") (pin "6") (pinfunction "6_6") (pintype "passive"))
      (node (ref "R5") (pin "1") (pinfunction "1_1") (pintype "passive"))
    )
    (net (code "59") (name "/USB_D_N") (class "Default")
      (node (ref "J1") (pin "12") (pinfunction "12_12") (pintype "passive"))
      (node (ref "R6") (pin "1") (pinfunction "1_1") (pintype "passive"))
    )
    (net (code "60") (name "/USB_D_P") (class "Default")
      (node (ref "J1") (pin "11") (pinfunction "11_11") (pintype "passive"))
      (node (ref "R7") (pin "1") (pinfunction "1_1") (pintype "passive"))
    )
    (net (code "61") (name "/USB_IN_D_N") (class "Default")
      (node (ref "R6") (pin "2") (pinfunction "2_2") (pintype "passive"))
      (node (ref "USB1") (pin "A7") (pinfunction "D-_A7") (pintype "passive"))
      (node (ref "USB1") (pin "B7") (pinfunction "D-_B7") (pintype "passive"))
    )
    (net (code "62") (name "/USB_IN_D_P") (class "Default")
      (node (ref "R7") (pin "2") (pinfunction "2_2") (pintype "passive"))
      (node (ref "USB1") (pin "A6") (pinfunction "D+_A6") (pintype "passive"))
      (node (ref "USB1") (pin "B6") (pinfunction "D+_B6") (pintype "passive"))
    )
    (net (code "63") (name "/USB_MIDI_IN") (class "Default")
      (node (ref "J1") (pin "15") (pinfunction "15_15") (pintype "passive"))
      (node (ref "S1") (pin "1") (pinfunction "1_1") (pintype "passive"))
    )
    (net (code "64") (name "5V") (class "Default")
      (node (ref "C1") (pin "2") (pinfunction "2_2") (pintype "passive"))
      (node (ref "C10") (pin "2") (pinfunction "2_2") (pintype "passive"))
      (node (ref "C2") (pin "2") (pinfunction "2_2") (pintype "passive"))
      (node (ref "C3") (pin "2") (pinfunction "2_2") (pintype "passive"))
      (node (ref "C4") (pin "2") (pinfunction "2_2") (pintype "passive"))
      (node (ref "C5") (pin "2") (pinfunction "2_2") (pintype "passive"))
      (node (ref "D1") (pin "1") (pinfunction "A_1") (pintype "passive"))
      (node (ref "D2") (pin "2") (pinfunction "K_2") (pintype "passive"))
      (node (ref "J1") (pin "1") (pinfunction "1_1") (pintype "passive"))
      (node (ref "J1") (pin "2") (pinfunction "2_2") (pintype "passive"))
      (node (ref "J2") (pin "1") (pinfunction "1_1") (pintype "passive"))
      (node (ref "J2") (pin "2") (pinfunction "2_2") (pintype "passive"))
      (node (ref "R10") (pin "1") (pinfunction "1_1") (pintype "passive"))
      (node (ref "TP5") (pin "1") (pinfunction "1_1") (pintype "passive"))
      (node (ref "U1") (pin "1") (pinfunction "VIN_1") (pintype "passive"))
      (node (ref "U1") (pin "3") (pinfunction "EN_3") (pintype "passive"))
      (node (ref "U2") (pin "4") (pinfunction "IN_4") (pintype "passive"))
      (node (ref "U4") (pin "24") (pinfunction "VU_24") (pintype "passive"))
    )
    (net (code "65") (name "A3V3") (class "Default")
      (node (ref "C13") (pin "1") (pinfunction "1_1") (pintype "passive"))
      (node (ref "C15") (pin "1") (pinfunction "1_1") (pintype "passive"))
      (node (ref "C23") (pin "2") (pinfunction "2_2") (pintype "passive"))
      (node (ref "C6") (pin "2") (pinfunction "2_2") (pintype "passive"))
      (node (ref "C7") (pin "2") (pinfunction "2_2") (pintype "passive"))
      (node (ref "FB1") (pin "2") (pinfunction "2_2") (pintype "passive"))
      (node (ref "FB3") (pin "1") (pintype "passive"))
      (node (ref "R22") (pin "1") (pinfunction "1_1") (pintype "passive"))
      (node (ref "R23") (pin "1") (pinfunction "1_1") (pintype "passive"))
      (node (ref "R34") (pin "1") (pinfunction "1_1") (pintype "passive"))
      (node (ref "TP7") (pin "1") (pinfunction "1_1") (pintype "passive"))
      (node (ref "U1") (pin "5") (pinfunction "VOUT_5") (pintype "passive"))
      (node (ref "U5") (pin "4") (pinfunction "VDDD_4") (pintype "passive"))
    )
    (net (code "66") (name "D3V3") (class "Default")
      (node (ref "C11") (pin "2") (pinfunction "2_2") (pintype "passive"))
      (node (ref "C12") (pin "2") (pinfunction "2_2") (pintype "passive"))
      (node (ref "C33") (pin "2") (pinfunction "2_2") (pintype "passive"))
      (node (ref "C34") (pin "2") (pinfunction "2_2") (pintype "passive"))
      (node (ref "C9") (pin "2") (pinfunction "2_2") (pintype "passive"))
      (node (ref "J1") (pin "4") (pinfunction "4_4") (pintype "passive"))
      (node (ref "J1") (pin "5") (pinfunction "5_5") (pintype "passive"))
      (node (ref "J2") (pin "4") (pinfunction "4_4") (pintype "passive"))
      (node (ref "J2") (pin "5") (pinfunction "5_5") (pintype "passive"))
      (node (ref "L1") (pin "2") (pinfunction "2_2") (pintype "passive"))
      (node (ref "R11") (pin "1") (pinfunction "1_1") (pintype "passive"))
      (node (ref "R2") (pin "2") (pinfunction "2_2") (pintype "passive"))
      (node (ref "R9") (pin "2") (pinfunction "2_2") (pintype "passive"))
      (node (ref "TP10") (pin "1") (pinfunction "1_1") (pintype "passive"))
      (node (ref "U6") (pin "3") (pinfunction "A2_3") (pintype "passive"))
      (node (ref "U6") (pin "8") (pinfunction "VCC_8") (pintype "passive"))
    )
    (net (code "67") (name "GND") (class "Default")
      (node (ref "C1") (pin "1") (pinfunction "1_1") (pintype "passive"))
      (node (ref "C10") (pin "1") (pinfunction "1_1") (pintype "passive"))
      (node (ref "C12") (pin "1") (pinfunction "1_1") (pintype "passive"))
      (node (ref "C13") (pin "2") (pinfunction "2_2") (pintype "passive"))
      (node (ref "C15") (pin "2") (pinfunction "2_2") (pintype "passive"))
      (node (ref "C2") (pin "1") (pinfunction "1_1") (pintype "passive"))
      (node (ref "C23") (pin "1") (pinfunction "1_1") (pintype "passive"))
      (node (ref "C3") (pin "1") (pinfunction "1_1") (pintype "passive"))
      (node (ref "C33") (pin "1") (pinfunction "1_1") (pintype "passive"))
      (node (ref "C34") (pin "1") (pinfunction "1_1") (pintype "passive"))
      (node (ref "C4") (pin "1") (pinfunction "1_1") (pintype "passive"))
      (node (ref "C5") (pin "1") (pinfunction "1_1") (pintype "passive"))
      (node (ref "C6") (pin "1") (pinfunction "1_1") (pintype "passive"))
      (node (ref "C7") (pin "1") (pinfunction "1_1") (pintype "passive"))
      (node (ref "C8") (pin "1") (pinfunction "1_1") (pintype "passive"))
      (node (ref "C9") (pin "1") (pinfunction "1_1") (pintype "passive"))
      (node (ref "CN1") (pin "4") (pinfunction "4_4") (pintype "passive"))
      (node (ref "FB2") (pin "2") (pinfunction "2_2") (pintype "passive"))
      (node (ref "FB4") (pin "1") (pintype "passive"))
      (node (ref "J1") (pin "0") (pinfunction "GND_0") (pintype "passive"))
      (node (ref "J1") (pin "10") (pinfunction "10_10") (pintype "passive"))
      (node (ref "J1") (pin "13") (pinfunction "13_13") (pintype "passive"))
      (node (ref "J1") (pin "14") (pinfunction "14_14") (pintype "passive"))
      (node (ref "J1") (pin "16") (pinfunction "16_16") (pintype "passive"))
      (node (ref "J1") (pin "21") (pinfunction "21_21") (pintype "passive"))
      (node (ref "J1") (pin "3") (pinfunction "3_3") (pintype "passive"))
      (node (ref "J1") (pin "6") (pinfunction "6_6") (pintype "passive"))
      (node (ref "J1") (pin "9") (pinfunction "9_9") (pintype "passive"))
      (node (ref "J2") (pin "0") (pinfunction "GND_0") (pintype "passive"))
      (node (ref "J2") (pin "3") (pinfunction "3_3") (pintype "passive"))
      (node (ref "J2") (pin "30") (pinfunction "30_30") (pintype "passive"))
      (node (ref "J2") (pin "6") (pinfunction "6_6") (pintype "passive"))
      (node (ref "JP1") (pin "3") (pinfunction "3_3") (pintype "passive"))
      (node (ref "R1") (pin "1") (pinfunction "1_1") (pintype "passive"))
      (node (ref "R12") (pin "2") (pinfunction "2_2") (pintype "passive"))
      (node (ref "R13") (pin "1") (pinfunction "1_1") (pintype "passive"))
      (node (ref "R14") (pin "1") (pinfunction "1_1") (pintype "passive"))
      (node (ref "R15") (pin "1") (pinfunction "1_1") (pintype "passive"))
      (node (ref "R16") (pin "1") (pinfunction "1_1") (pintype "passive"))
      (node (ref "R19") (pin "2") (pinfunction "2_2") (pintype "passive"))
      (node (ref "R27") (pin "2") (pinfunction "2_2") (pintype "passive"))
      (node (ref "R28") (pin "2") (pinfunction "2_2") (pintype "passive"))
      (node (ref "R29") (pin "2") (pinfunction "2_2") (pintype "passive"))
      (node (ref "R3") (pin "2") (pinfunction "2_2") (pintype "passive"))
      (node (ref "R35") (pin "1") (pinfunction "1_1") (pintype "passive"))
      (node (ref "R4") (pin "2") (pinfunction "2_2") (pintype "passive"))
      (node (ref "TP3") (pin "1") (pinfunction "1_1") (pintype "passive"))
      (node (ref "TP4") (pin "1") (pinfunction "1_1") (pintype "passive"))
      (node (ref "U1") (pin "2") (pinfunction "GND_2") (pintype "passive"))
      (node (ref "U2") (pin "2") (pinfunction "GND_2") (pintype "passive"))
      (node (ref "U3") (pin "4") (pinfunction "Emiter_4") (pintype "passive"))
      (node (ref "U4") (pin "25") (pinfunction "GND_25") (pintype "passive"))
      (node (ref "U5") (pin "5") (pinfunction "VSSD_5") (pintype "passive"))
      (node (ref "U6") (pin "1") (pinfunction "A0_1") (pintype "passive"))
      (node (ref "U6") (pin "2") (pinfunction "A1_2") (pintype "passive"))
      (node (ref "U6") (pin "4") (pinfunction "GND_4") (pintype "passive"))
      (node (ref "U6") (pin "7") (pinfunction "WP_7") (pintype "passive"))
      (node (ref "USB1") (pin "1") (pinfunction "SH1_1") (pintype "passive"))
      (node (ref "USB1") (pin "2") (pinfunction "SH2_2") (pintype "passive"))
      (node (ref "USB1") (pin "3") (pinfunction "SH3_3") (pintype "passive"))
      (node (ref "USB1") (pin "4") (pinfunction "SH4_4") (pintype "passive"))
      (node (ref "USB1") (pin "A1") (pinfunction "GND_A1") (pintype "passive"))
      (node (ref "USB1") (pin "A12") (pinfunction "GND_A12") (pintype "passive"))
      (node (ref "USB1") (pin "B1") (pinfunction "GND_B1") (pintype "passive"))
      (node (ref "USB1") (pin "B12") (pinfunction "GND_B12") (pintype "passive"))
    )
    (net (code "68") (name "IN_AGND") (class "Default")
      (node (ref "C24") (pin "1") (pinfunction "1_1") (pintype "passive"))
      (node (ref "C25") (pin "1") (pinfunction "1_1") (pintype "passive"))
      (node (ref "C27") (pin "1") (pinfunction "1_1") (pintype "passive"))
      (node (ref "C29") (pin "1") (pinfunction "1_1") (pintype "passive"))
      (node (ref "C30") (pin "1") (pinfunction "1_1") (pintype "passive"))
      (node (ref "C31") (pin "1") (pinfunction "1_1") (pintype "passive"))
      (node (ref "C32") (pin "1") (pinfunction "1_1") (pintype "passive"))
      (node (ref "CN4") (pin "4") (pinfunction "4_4") (pintype "passive"))
      (node (ref "FB4") (pin "2") (pinfunction "2_2") (pintype "passive"))
      (node (ref "R31") (pin "2") (pinfunction "2_2") (pintype "passive"))
      (node (ref "R33") (pin "2") (pinfunction "2_2") (pintype "passive"))
      (node (ref "U7") (pin "9") (pinfunction "GND_9") (pintype "passive"))
    )
    (net (code "69") (name "Net-(C17-Pad2)") (class "Default")
      (node (ref "C17") (pin "2") (pinfunction "2_2") (pintype "passive"))
      (node (ref "R17") (pin "2") (pinfunction "2_2") (pintype "passive"))
      (node (ref "R18") (pin "1") (pinfunction "1_1") (pintype "passive"))
    )
    (net (code "70") (name "Net-(C19-Pad2)") (class "Default")
      (node (ref "C19") (pin "2") (pinfunction "2_2") (pintype "passive"))
      (node (ref "R21") (pin "2") (pinfunction "2_2") (pintype "passive"))
      (node (ref "R26") (pin "1") (pinfunction "1_1") (pintype "passive"))
    )
    (net (code "71") (name "Net-(C26-Pad1)") (class "Default")
      (node (ref "C26") (pin "1") (pinfunction "1_1") (pintype "passive"))
      (node (ref "R30") (pin "2") (pinfunction "2_2") (pintype "passive"))
      (node (ref "R31") (pin "1") (pinfunction "1_1") (pintype "passive"))
    )
    (net (code "72") (name "Net-(C28-Pad1)") (class "Default")
      (node (ref "C28") (pin "1") (pinfunction "1_1") (pintype "passive"))
      (node (ref "R32") (pin "1") (pinfunction "1_1") (pintype "passive"))
      (node (ref "R33") (pin "1") (pinfunction "1_1") (pintype "passive"))
    )
    (net (code "73") (name "Net-(D1-K)") (class "Default")
      (node (ref "D1") (pin "2") (pinfunction "K_2") (pintype "passive"))
      (node (ref "R1") (pin "2") (pinfunction "2_2") (pintype "passive"))
    )
    (net (code "74") (name "Net-(D3-K)") (class "Default")
      (node (ref "D3") (pin "2") (pinfunction "K_2") (pintype "passive"))
      (node (ref "R8") (pin "2") (pinfunction "2_2") (pintype "passive"))
      (node (ref "U3") (pin "1") (pinfunction "Anaode_1") (pintype "passive"))
    )
    (net (code "75") (name "Net-(D4-K)") (class "Default")
      (node (ref "D4") (pin "2") (pinfunction "K_2") (pintype "passive"))
      (node (ref "R13") (pin "2") (pinfunction "2_2") (pintype "passive"))
    )
    (net (code "76") (name "Net-(D5-K)") (class "Default")
      (node (ref "D5") (pin "2") (pinfunction "K_2") (pintype "passive"))
      (node (ref "R14") (pin "2") (pinfunction "2_2") (pintype "passive"))
    )
    (net (code "77") (name "Net-(D6-K)") (class "Default")
      (node (ref "D6") (pin "2") (pinfunction "K_2") (pintype "passive"))
      (node (ref "R15") (pin "2") (pinfunction "2_2") (pintype "passive"))
    )
    (net (code "78") (name "Net-(D7-K)") (class "Default")
      (node (ref "D7") (pin "2") (pinfunction "K_2") (pintype "passive"))
      (node (ref "R16") (pin "2") (pinfunction "2_2") (pintype "passive"))
    )
    (net (code "79") (name "Net-(U1-BYPASS)") (class "Default")
      (node (ref "C8") (pin "2") (pinfunction "2_2") (pintype "passive"))
      (node (ref "U1") (pin "4") (pinfunction "BYPASS_4") (pintype "passive"))
    )
    (net (code "80") (name "Net-(U2-EN)") (class "Default")
      (node (ref "R10") (pin "2") (pinfunction "2_2") (pintype "passive"))
      (node (ref "U2") (pin "1") (pinfunction "EN_1") (pintype "passive"))
    )
    (net (code "81") (name "Net-(U2-FB)") (class "Default")
      (node (ref "C11") (pin "1") (pinfunction "1_1") (pintype "passive"))
      (node (ref "R11") (pin "2") (pinfunction "2_2") (pintype "passive"))
      (node (ref "R12") (pin "1") (pinfunction "1_1") (pintype "passive"))
      (node (ref "U2") (pin "5") (pinfunction "FB_5") (pintype "passive"))
    )
    (net (code "82") (name "Net-(U2-Out)") (class "Default")
      (node (ref "L1") (pin "1") (pintype "passive"))
      (node (ref "U2") (pin "3") (pinfunction "Out_3") (pintype "passive"))
    )
    (net (code "83") (name "Net-(U5-BCK)") (class "Default")
      (node (ref "R20") (pin "2") (pinfunction "2_2") (pintype "passive"))
      (node (ref "U5") (pin "1") (pinfunction "BCK_1") (pintype "passive"))
    )
    (net (code "84") (name "Net-(U5-DATA1)") (class "Default")
      (node (ref "R25") (pin "2") (pinfunction "2_2") (pintype "passive"))
      (node (ref "U5") (pin "3") (pinfunction "DATA1_3") (pintype "passive"))
    )
    (net (code "85") (name "Net-(U5-DEEM{slash}CLKOUT)") (class "Default")
      (node (ref "R28") (pin "1") (pinfunction "1_1") (pintype "passive"))
      (node (ref "TP20") (pin "1") (pinfunction "1_1") (pintype "passive"))
      (node (ref "U5") (pin "9") (pinfunction "DEEM/CLKOUT_9") (pintype "passive"))
    )
    (net (code "86") (name "Net-(U5-PLL0)") (class "Default")
      (node (ref "R29") (pin "1") (pinfunction "1_1") (pintype "passive"))
      (node (ref "TP21") (pin "1") (pinfunction "1_1") (pintype "passive"))
      (node (ref "U5") (pin "10") (pinfunction "PLL0_10") (pintype "passive"))
    )
    (net (code "87") (name "Net-(U5-SYSCLK{slash}PLL1)") (class "Default")
      (node (ref "R19") (pin "1") (pinfunction "1_1") (pintype "passive"))
      (node (ref "TP14") (pin "1") (pinfunction "1_1") (pintype "passive"))
      (node (ref "U5") (pin "6") (pinfunction "SYSCLK/PLL1_6") (pintype "passive"))
    )
    (net (code "88") (name "Net-(U5-VDDA)") (class "Default")
      (node (ref "C14") (pin "1") (pinfunction "1_1") (pintype "passive"))
      (node (ref "C16") (pin "1") (pinfunction "1_1") (pintype "passive"))
      (node (ref "FB1") (pin "1") (pintype "passive"))
      (node (ref "U5") (pin "13") (pinfunction "VDDA_13") (pintype "passive"))
      (node (ref "U5") (pin "15") (pinfunction "VSSA_15") (pintype "passive"))
    )
    (net (code "89") (name "Net-(U5-VOUTL)") (class "Default")
      (node (ref "C17") (pin "1") (pinfunction "1_1") (pintype "passive"))
      (node (ref "U5") (pin "14") (pinfunction "VOUTL_14") (pintype "passive"))
    )
    (net (code "90") (name "Net-(U5-VOUTR)") (class "Default")
      (node (ref "C19") (pin "1") (pinfunction "1_1") (pintype "passive"))
      (node (ref "U5") (pin "16") (pinfunction "VOUTR_16") (pintype "passive"))
    )
    (net (code "91") (name "Net-(U5-VREF(DAC))") (class "Default")
      (node (ref "C21") (pin "2") (pinfunction "2_2") (pintype "passive"))
      (node (ref "C22") (pin "2") (pinfunction "2_2") (pintype "passive"))
      (node (ref "U5") (pin "12") (pinfunction "VREF(DAC)_12") (pintype "passive"))
    )
    (net (code "92") (name "Net-(U5-WS)") (class "Default")
      (node (ref "R24") (pin "2") (pinfunction "2_2") (pintype "passive"))
      (node (ref "U5") (pin "2") (pinfunction "WS_2") (pintype "passive"))
    )
    (net (code "93") (name "Net-(U7-AINL)") (class "Default")
      (node (ref "C28") (pin "2") (pinfunction "2_2") (pintype "passive"))
      (node (ref "C31") (pin "2") (pinfunction "2_2") (pintype "passive"))
      (node (ref "U7") (pin "6") (pinfunction "AINL_6") (pintype "passive"))
    )
    (net (code "94") (name "Net-(U7-AINR)") (class "Default")
      (node (ref "C26") (pin "2") (pinfunction "2_2") (pintype "passive"))
      (node (ref "C27") (pin "2") (pinfunction "2_2") (pintype "passive"))
      (node (ref "U7") (pin "8") (pinfunction "AINR_8") (pintype "passive"))
    )
    (net (code "95") (name "Net-(U7-FLR+)") (class "Default")
      (node (ref "C32") (pin "2") (pinfunction "2_2") (pintype "passive"))
      (node (ref "U7") (pin "5") (pinfunction "FLR+_5") (pintype "passive"))
    )
    (net (code "96") (name "Net-(U7-VA)") (class "Default")
      (node (ref "C24") (pin "2") (pinfunction "2_2") (pintype "passive"))
      (node (ref "C25") (pin "2") (pinfunction "2_2") (pintype "passive"))
      (node (ref "FB3") (pin "2") (pinfunction "2_2") (pintype "passive"))
      (node (ref "U7") (pin "10") (pinfunction "VA_10") (pintype "passive"))
    )
    (net (code "97") (name "Net-(U7-VQ)") (class "Default")
      (node (ref "C29") (pin "2") (pinfunction "2_2") (pintype "passive"))
      (node (ref "C30") (pin "2") (pinfunction "2_2") (pintype "passive"))
      (node (ref "U7") (pin "7") (pinfunction "VQ_7") (pintype "passive"))
    )
    (net (code "98") (name "Net-(USB1-CC1)") (class "Default")
      (node (ref "R3") (pin "1") (pinfunction "1_1") (pintype "passive"))
      (node (ref "USB1") (pin "A5") (pinfunction "CC1_A5") (pintype "passive"))
    )
    (net (code "99") (name "Net-(USB1-CC2)") (class "Default")
      (node (ref "R4") (pin "1") (pinfunction "1_1") (pintype "passive"))
      (node (ref "USB1") (pin "B5") (pinfunction "CC2_B5") (pintype "passive"))
    )
    (net (code "100") (name "OUT_AGND") (class "Default")
      (node (ref "C14") (pin "2") (pinfunction "2_2") (pintype "passive"))
      (node (ref "C16") (pin "2") (pinfunction "2_2") (pintype "passive"))
      (node (ref "C18") (pin "1") (pinfunction "1_1") (pintype "passive"))
      (node (ref "C20") (pin "1") (pinfunction "1_1") (pintype "passive"))
      (node (ref "C21") (pin "1") (pinfunction "1_1") (pintype "passive"))
      (node (ref "C22") (pin "1") (pinfunction "1_1") (pintype "passive"))
      (node (ref "CN3") (pin "4") (pinfunction "4_4") (pintype "passive"))
      (node (ref "FB2") (pin "1") (pintype "passive"))
      (node (ref "R18") (pin "2") (pinfunction "2_2") (pintype "passive"))
      (node (ref "R26") (pin "2") (pinfunction "2_2") (pintype "passive"))
    )
    (net (code "101") (name "VBUS") (class "Default")
      (node (ref "D2") (pin "1") (pinfunction "A_1") (pintype "passive"))
      (node (ref "USB1") (pin "A4") (pinfunction "VBUS_A4") (pintype "passive"))
      (node (ref "USB1") (pin "A9") (pinfunction "VBUS_A9") (pintype "passive"))
      (node (ref "USB1") (pin "B4") (pinfunction "VBUS_B4") (pintype "passive"))
      (node (ref "USB1") (pin "B9") (pinfunction "VBUS_B9") (pintype "passive"))
    )
    (net (code "102") (name "unconnected-(J1-Pad26)") (class "Default")
      (node (ref "J1") (pin "26") (pinfunction "26_26") (pintype "passive+no_connect"))
    )
    (net (code "103") (name "unconnected-(J1-Pad27)") (class "Default")
      (node (ref "J1") (pin "27") (pinfunction "27_27") (pintype "passive+no_connect"))
    )
    (net (code "104") (name "unconnected-(J1-Pad28)") (class "Default")
      (node (ref "J1") (pin "28") (pinfunction "28_28") (pintype "passive+no_connect"))
    )
    (net (code "105") (name "unconnected-(J1-Pad29)") (class "Default")
      (node (ref "J1") (pin "29") (pinfunction "29_29") (pintype "passive+no_connect"))
    )
    (net (code "106") (name "unconnected-(J1-Pad30)") (class "Default")
      (node (ref "J1") (pin "30") (pinfunction "30_30") (pintype "passive+no_connect"))
    )
    (net (code "107") (name "unconnected-(SP1-Pad1)") (class "Default")
      (node (ref "SP1") (pin "1") (pinfunction "1_1") (pintype "passive"))
    )
    (net (code "108") (name "unconnected-(SP2-Pad1)") (class "Default")
      (node (ref "SP2") (pin "1") (pinfunction "1_1") (pintype "passive"))
    )
    (net (code "109") (name "unconnected-(SP3-Pad1)") (class "Default")
      (node (ref "SP3") (pin "1") (pinfunction "1_1") (pintype "passive"))
    )
    (net (code "110") (name "unconnected-(SP4-Pad1)") (class "Default")
      (node (ref "SP4") (pin "1") (pinfunction "1_1") (pintype "passive"))
    )
    (net (code "111") (name "unconnected-(U3-Base-Pad6)") (class "Default")
      (node (ref "U3") (pin "6") (pinfunction "Base_6") (pintype "passive"))
    )
    (net (code "112") (name "unconnected-(USB1-RX1+-PadB11)") (class "Default")
      (node (ref "USB1") (pin "B11") (pinfunction "RX1+_B11") (pintype "passive"))
    )
    (net (code "113") (name "unconnected-(USB1-RX1--PadB10)") (class "Default")
      (node (ref "USB1") (pin "B10") (pinfunction "RX1-_B10") (pintype "passive"))
    )
    (net (code "114") (name "unconnected-(USB1-RX2+-PadA11)") (class "Default")
      (node (ref "USB1") (pin "A11") (pinfunction "RX2+_A11") (pintype "passive"))
    )
    (net (code "115") (name "unconnected-(USB1-RX2--PadA10)") (class "Default")
      (node (ref "USB1") (pin "A10") (pinfunction "RX2-_A10") (pintype "passive"))
    )
    (net (code "116") (name "unconnected-(USB1-SBU1-PadA8)") (class "Default")
      (node (ref "USB1") (pin "A8") (pinfunction "SBU1_A8") (pintype "passive"))
    )
    (net (code "117") (name "unconnected-(USB1-SBU2-PadB8)") (class "Default")
      (node (ref "USB1") (pin "B8") (pinfunction "SBU2_B8") (pintype "passive"))
    )
    (net (code "118") (name "unconnected-(USB1-TX1+-PadA2)") (class "Default")
      (node (ref "USB1") (pin "A2") (pinfunction "TX1+_A2") (pintype "passive"))
    )
    (net (code "119") (name "unconnected-(USB1-TX1--PadA3)") (class "Default")
      (node (ref "USB1") (pin "A3") (pinfunction "TX1-_A3") (pintype "passive"))
    )
    (net (code "120") (name "unconnected-(USB1-TX2+-PadB2)") (class "Default")
      (node (ref "USB1") (pin "B2") (pinfunction "TX2+_B2") (pintype "passive"))
    )
    (net (code "121") (name "unconnected-(USB1-TX2--PadB3)") (class "Default")
      (node (ref "USB1") (pin "B3") (pinfunction "TX2-_B3") (pintype "passive"))
    )
  )
)
